# core-feather-shield-adc-imu-advanced_v1_.net
KiCad netlist of a schematic drawn in EAGLE
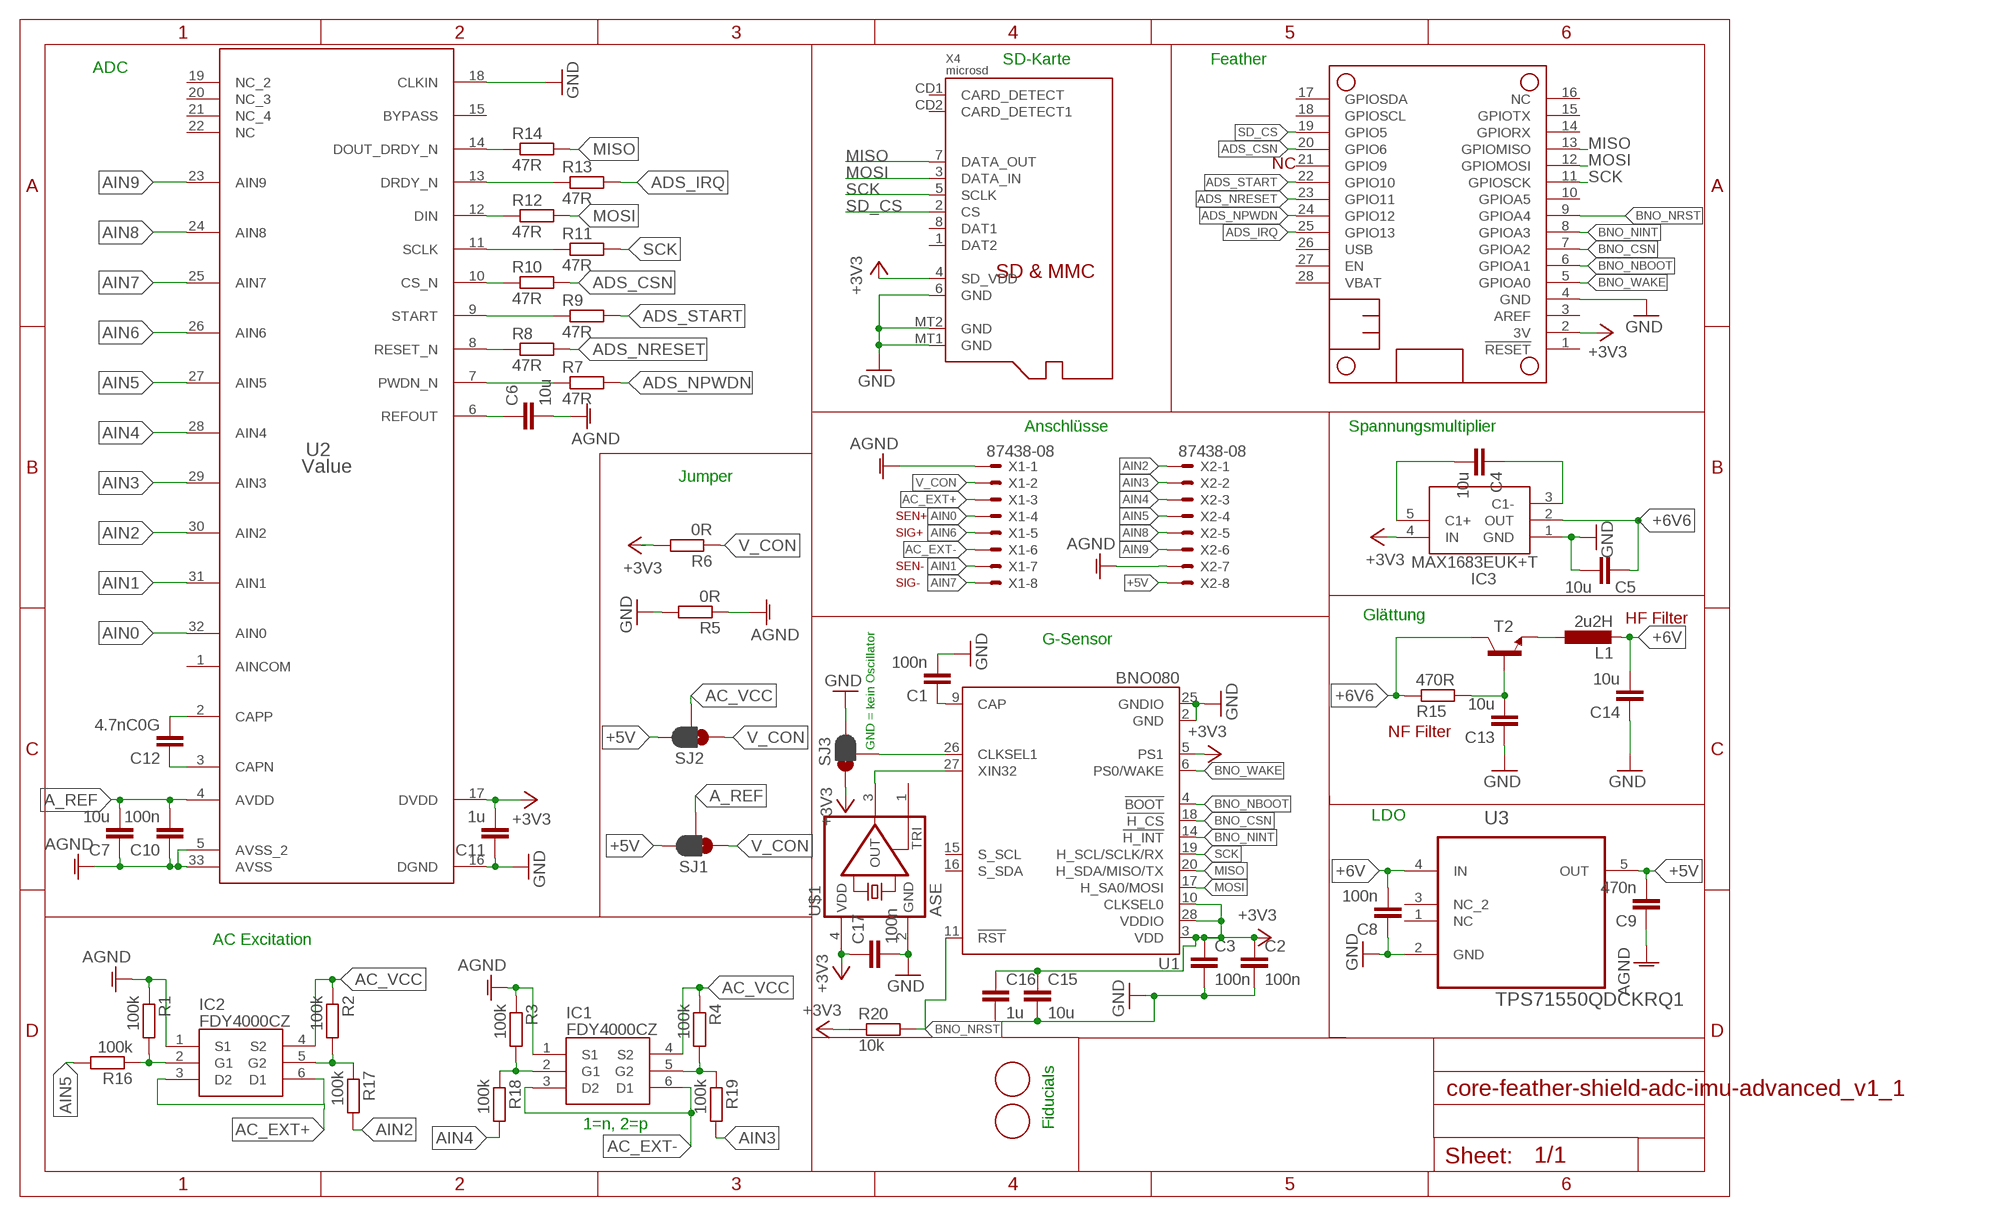
[diagram p0: schematic, sheet 1]

(export (version "E")
  (design (tool "Eeschema 10.0.6"))
  (components
    (comp (ref "C1")
      (value "100n")
      (footprint "eagle-import:C0805")
      (libsource (lib "eagle-import") (part "C-EUC0805"))
    )
    (comp (ref "C2")
      (value "100n")
      (footprint "eagle-import:C0805")
      (libsource (lib "eagle-import") (part "C-EUC0805"))
    )
    (comp (ref "C3")
      (value "100n")
      (footprint "eagle-import:C0805")
      (libsource (lib "eagle-import") (part "C-EUC0805"))
    )
    (comp (ref "C4")
      (value "10u")
      (footprint "eagle-import:C0805")
      (libsource (lib "eagle-import") (part "C-EUC0805"))
    )
    (comp (ref "C5")
      (value "10u")
      (footprint "eagle-import:C0805")
      (libsource (lib "eagle-import") (part "C-EUC0805"))
    )
    (comp (ref "C6")
      (value "10u")
      (footprint "eagle-import:C0805")
      (libsource (lib "eagle-import") (part "C-EUC0805"))
    )
    (comp (ref "C7")
      (value "10u")
      (footprint "eagle-import:C0805")
      (libsource (lib "eagle-import") (part "C-EUC0805"))
    )
    (comp (ref "C8")
      (value "100n")
      (footprint "eagle-import:C0805")
      (libsource (lib "eagle-import") (part "C-EUC0805"))
    )
    (comp (ref "C9")
      (value "470n")
      (footprint "eagle-import:C0805")
      (libsource (lib "eagle-import") (part "C-EUC0805"))
    )
    (comp (ref "C10")
      (value "100n")
      (footprint "eagle-import:C0805")
      (libsource (lib "eagle-import") (part "C-EUC0805"))
    )
    (comp (ref "C11")
      (value "1u")
      (footprint "eagle-import:C0805")
      (libsource (lib "eagle-import") (part "C-EUC0805"))
    )
    (comp (ref "C12")
      (value "4.7nC0G")
      (footprint "eagle-import:C0805")
      (libsource (lib "eagle-import") (part "C-EUC0805"))
    )
    (comp (ref "C13")
      (value "10u")
      (footprint "eagle-import:C0805")
      (libsource (lib "eagle-import") (part "C-EUC0805"))
    )
    (comp (ref "C14")
      (value "10u")
      (footprint "eagle-import:C0805")
      (libsource (lib "eagle-import") (part "C-EUC0805"))
    )
    (comp (ref "C15")
      (value "10u")
      (footprint "eagle-import:C0805")
      (libsource (lib "eagle-import") (part "C-EUC0805"))
    )
    (comp (ref "C16")
      (value "1u")
      (footprint "eagle-import:C0805")
      (libsource (lib "eagle-import") (part "C-EUC0805"))
    )
    (comp (ref "C17")
      (value "100n")
      (footprint "eagle-import:C0805")
      (libsource (lib "eagle-import") (part "C-EUC0805"))
    )
    (comp (ref "IC1")
      (value "FDY4000CZ")
      (footprint "eagle-import:SOTFL50P160X60-6N")
      (fields (field (name "MOUSER_PART_NUMBER") "512-FDY4000CZ") (field (name "RS_PART_NUMBER") "6710857"))
      (libsource (lib "eagle-import") (part "FDY4000CZ"))
    )
    (comp (ref "IC2")
      (value "FDY4000CZ")
      (footprint "eagle-import:SOTFL50P160X60-6N")
      (fields (field (name "MOUSER_PART_NUMBER") "512-FDY4000CZ") (field (name "RS_PART_NUMBER") "6710857"))
      (libsource (lib "eagle-import") (part "FDY4000CZ"))
    )
    (comp (ref "IC3")
      (value "MAX1683EUK+T")
      (footprint "eagle-import:SOT95P280X145-5N")
      (fields (field (name "MOUSER_PART_NUMBER") "700-MAX1683EUKT"))
      (libsource (lib "eagle-import") (part "MAX1683EUK+T"))
    )
    (comp (ref "L1")
      (value "2u2H")
      (footprint "eagle-import:L0805")
      (libsource (lib "eagle-import") (part "L-EUL0805"))
    )
    (comp (ref "MS1")
      (value "FEATHERWING")
      (footprint "eagle-import:FEATHERWING")
      (libsource (lib "eagle-import") (part "FEATHERWING"))
    )
    (comp (ref "R1")
      (value "100k")
      (footprint "eagle-import:R0805")
      (libsource (lib "eagle-import") (part "R-EU_R0805"))
    )
    (comp (ref "R2")
      (value "100k")
      (footprint "eagle-import:R0805")
      (libsource (lib "eagle-import") (part "R-EU_R0805"))
    )
    (comp (ref "R3")
      (value "100k")
      (footprint "eagle-import:R0805")
      (libsource (lib "eagle-import") (part "R-EU_R0805"))
    )
    (comp (ref "R4")
      (value "100k")
      (footprint "eagle-import:R0805")
      (libsource (lib "eagle-import") (part "R-EU_R0805"))
    )
    (comp (ref "R5")
      (value "0R")
      (footprint "eagle-import:R0805")
      (libsource (lib "eagle-import") (part "R-EU_R0805"))
    )
    (comp (ref "R6")
      (value "0R")
      (footprint "eagle-import:R0805")
      (libsource (lib "eagle-import") (part "R-EU_R0805"))
    )
    (comp (ref "R7")
      (value "47R")
      (footprint "eagle-import:R0805")
      (libsource (lib "eagle-import") (part "R-EU_R0805"))
    )
    (comp (ref "R8")
      (value "47R")
      (footprint "eagle-import:R0805")
      (libsource (lib "eagle-import") (part "R-EU_R0805"))
    )
    (comp (ref "R9")
      (value "47R")
      (footprint "eagle-import:R0805")
      (libsource (lib "eagle-import") (part "R-EU_R0805"))
    )
    (comp (ref "R10")
      (value "47R")
      (footprint "eagle-import:R0805")
      (libsource (lib "eagle-import") (part "R-EU_R0805"))
    )
    (comp (ref "R11")
      (value "47R")
      (footprint "eagle-import:R0805")
      (libsource (lib "eagle-import") (part "R-EU_R0805"))
    )
    (comp (ref "R12")
      (value "47R")
      (footprint "eagle-import:R0805")
      (libsource (lib "eagle-import") (part "R-EU_R0805"))
    )
    (comp (ref "R13")
      (value "47R")
      (footprint "eagle-import:R0805")
      (libsource (lib "eagle-import") (part "R-EU_R0805"))
    )
    (comp (ref "R14")
      (value "47R")
      (footprint "eagle-import:R0805")
      (libsource (lib "eagle-import") (part "R-EU_R0805"))
    )
    (comp (ref "R15")
      (value "470R")
      (footprint "eagle-import:R0805")
      (libsource (lib "eagle-import") (part "R-EU_R0805"))
    )
    (comp (ref "R16")
      (value "100k")
      (footprint "eagle-import:R0805")
      (libsource (lib "eagle-import") (part "R-EU_R0805"))
    )
    (comp (ref "R17")
      (value "100k")
      (footprint "eagle-import:R0805")
      (libsource (lib "eagle-import") (part "R-EU_R0805"))
    )
    (comp (ref "R18")
      (value "100k")
      (footprint "eagle-import:R0805")
      (libsource (lib "eagle-import") (part "R-EU_R0805"))
    )
    (comp (ref "R19")
      (value "100k")
      (footprint "eagle-import:R0805")
      (libsource (lib "eagle-import") (part "R-EU_R0805"))
    )
    (comp (ref "R20")
      (value "10k")
      (footprint "eagle-import:R0805")
      (libsource (lib "eagle-import") (part "R-EU_R0805"))
    )
    (comp (ref "SJ1")
      (value "JUMPER_PAD-3-1&2_NC_BY_PASTE")
      (footprint "eagle-import:PAD-HUMPER-3-1&2_NC_BY_PASTE_YES_SILK_FULL_BOX")
      (libsource (lib "eagle-import") (part "JUMPER_PAD-3-1&2_NC_BY_PASTE"))
    )
    (comp (ref "SJ2")
      (value "JUMPER_PAD-3-1&2_NC_BY_PASTE")
      (footprint "eagle-import:PAD-HUMPER-3-1&2_NC_BY_PASTE_YES_SILK_FULL_BOX")
      (libsource (lib "eagle-import") (part "JUMPER_PAD-3-1&2_NC_BY_PASTE"))
    )
    (comp (ref "SJ3")
      (value "JUMPER_PAD-3-1&2_NC_BY_PASTE")
      (footprint "eagle-import:PAD-HUMPER-3-1&2_NC_BY_PASTE_YES_SILK_FULL_BOX")
      (libsource (lib "eagle-import") (part "JUMPER_PAD-3-1&2_NC_BY_PASTE"))
    )
    (comp (ref "T2")
      (value "BC808-NPN-SOT23-BEC")
      (footprint "eagle-import:SOT23-BEC")
      (libsource (lib "eagle-import") (part "-NPN-SOT23-BECBC808"))
    )
    (comp (ref "U$1")
      (value "ASE")
      (footprint "eagle-import:ASE")
      (libsource (lib "eagle-import") (part "ASE"))
    )
    (comp (ref "U$8")
      (value "FIDUCIAL")
      (footprint "eagle-import:FIDUCIAL_1MM")
      (libsource (lib "eagle-import") (part "FIDUCIAL"))
    )
    (comp (ref "U$9")
      (value "FIDUCIAL")
      (footprint "eagle-import:FIDUCIAL_1MM")
      (libsource (lib "eagle-import") (part "FIDUCIAL"))
    )
    (comp (ref "U1")
      (value "BNO080")
      (footprint "eagle-import:LGA-28")
      (fields (field (name "MF") "Hillcrest Laboratories,"))
      (libsource (lib "eagle-import") (part "BNO080"))
    )
    (comp (ref "U2")
      (value "Value")
      (footprint "eagle-import:RHB0032E")
      (fields (field (name "MANUFACTURER") "Texas Instruments") (field (name "PARTNUMBER") "ADS1261IRHBR"))
      (libsource (lib "eagle-import") (part "ADS1261IRHBR"))
    )
    (comp (ref "U3")
      (value "TPS71550QDCKRQ1")
      (footprint "eagle-import:SOT65P210X110-5N")
      (fields (field (name "MF") "Texas Instruments"))
      (libsource (lib "eagle-import") (part "TPS71550QDCKRQ1"))
    )
    (comp (ref "X1")
      (value "87438-08")
      (footprint "eagle-import:87438-08")
      (fields (field (name "MF") "MOLEX") (field (name "SPICEPREFIX") "X"))
      (libsource (lib "eagle-import") (part "87438-08"))
    )
    (comp (ref "X2")
      (value "87438-08")
      (footprint "eagle-import:87438-08")
      (fields (field (name "MF") "MOLEX") (field (name "SPICEPREFIX") "X"))
      (libsource (lib "eagle-import") (part "87438-08"))
    )
    (comp (ref "X4")
      (value "microsd")
      (footprint "eagle-import:MICROSD")
      (libsource (lib "eagle-import") (part "MICROSD"))
    )
  )
  (nets
    (net (code "1") (name "+3V3") (class "Default")
      (node (ref "C11") (pin "2") (pinfunction "2_2") (pintype "passive"))
      (node (ref "C15") (pin "1") (pinfunction "1_1") (pintype "passive"))
      (node (ref "C16") (pin "1") (pinfunction "1_1") (pintype "passive"))
      (node (ref "C17") (pin "1") (pinfunction "1_1") (pintype "passive"))
      (node (ref "C2") (pin "1") (pinfunction "1_1") (pintype "passive"))
      (node (ref "C3") (pin "1") (pinfunction "1_1") (pintype "passive"))
      (node (ref "IC3") (pin "4") (pinfunction "IN_4") (pintype "input"))
      (node (ref "MS1") (pin "2") (pinfunction "3V_2") (pintype "power_in"))
      (node (ref "R20") (pin "1") (pinfunction "1_1") (pintype "passive"))
      (node (ref "R6") (pin "2") (pinfunction "2_2") (pintype "passive"))
      (node (ref "SJ3") (pin "3") (pinfunction "3_3") (pintype "passive"))
      (node (ref "U$1") (pin "4") (pinfunction "VDD_4") (pintype "power_in"))
      (node (ref "U1") (pin "10") (pinfunction "CLKSEL0_10") (pintype "bidirectional"))
      (node (ref "U1") (pin "28") (pinfunction "VDDIO_28") (pintype "bidirectional"))
      (node (ref "U1") (pin "3") (pinfunction "VDD_3") (pintype "bidirectional"))
      (node (ref "U1") (pin "5") (pinfunction "PS1_5") (pintype "bidirectional"))
      (node (ref "U2") (pin "17") (pinfunction "DVDD_17") (pintype "power_in"))
      (node (ref "X4") (pin "4") (pinfunction "SD_VDD_4") (pintype "power_in"))
    )
    (net (code "2") (name "+5V") (class "Default")
      (node (ref "C9") (pin "2") (pinfunction "2_2") (pintype "passive"))
      (node (ref "SJ1") (pin "1") (pinfunction "1_1") (pintype "passive"))
      (node (ref "SJ2") (pin "1") (pinfunction "1_1") (pintype "passive"))
      (node (ref "U3") (pin "5") (pinfunction "OUT_5") (pintype "output"))
      (node (ref "X2") (pin "8") (pinfunction "S_8") (pintype "passive"))
    )
    (net (code "3") (name "+6V") (class "Default")
      (node (ref "C14") (pin "2") (pinfunction "2_2") (pintype "passive"))
      (node (ref "C8") (pin "2") (pinfunction "2_2") (pintype "passive"))
      (node (ref "L1") (pin "2") (pinfunction "2_2") (pintype "passive"))
      (node (ref "U3") (pin "4") (pinfunction "IN_4") (pintype "power_in"))
    )
    (net (code "4") (name "+6V6") (class "Default")
      (node (ref "C5") (pin "1") (pinfunction "1_1") (pintype "passive"))
      (node (ref "IC3") (pin "2") (pinfunction "OUT_2") (pintype "output"))
      (node (ref "R15") (pin "2") (pinfunction "2_2") (pintype "passive"))
      (node (ref "T2") (pin "C") (pinfunction "C_C") (pintype "passive"))
    )
    (net (code "5") (name "/USB") (class "Default")
      (node (ref "MS1") (pin "26") (pinfunction "USB_26") (pintype "power_in"))
    )
    (net (code "6") (name "/VBAT") (class "Default")
      (node (ref "MS1") (pin "28") (pinfunction "VBAT_28") (pintype "power_in"))
    )
    (net (code "7") (name "AC_EXT+") (class "Default")
      (node (ref "IC2") (pin "3") (pinfunction "D2_3") (pintype "bidirectional"))
      (node (ref "IC2") (pin "6") (pinfunction "D1_6") (pintype "bidirectional"))
      (node (ref "X1") (pin "3") (pinfunction "S_3") (pintype "passive"))
    )
    (net (code "8") (name "AC_EXT-") (class "Default")
      (node (ref "IC1") (pin "3") (pinfunction "D2_3") (pintype "bidirectional"))
      (node (ref "IC1") (pin "6") (pinfunction "D1_6") (pintype "bidirectional"))
      (node (ref "X1") (pin "6") (pinfunction "S_6") (pintype "passive"))
    )
    (net (code "9") (name "AC_VCC") (class "Default")
      (node (ref "IC1") (pin "4") (pinfunction "S2_4") (pintype "bidirectional"))
      (node (ref "IC2") (pin "4") (pinfunction "S2_4") (pintype "bidirectional"))
      (node (ref "R2") (pin "1") (pinfunction "1_1") (pintype "passive"))
      (node (ref "R4") (pin "1") (pinfunction "1_1") (pintype "passive"))
      (node (ref "SJ2") (pin "2") (pinfunction "2_2") (pintype "passive"))
    )
    (net (code "10") (name "ADS_CSN") (class "Default")
      (node (ref "MS1") (pin "20") (pinfunction "GPIO6_20") (pintype "bidirectional"))
      (node (ref "R10") (pin "2") (pinfunction "2_2") (pintype "passive"))
    )
    (net (code "11") (name "ADS_IRQ") (class "Default")
      (node (ref "MS1") (pin "25") (pinfunction "GPIO13_25") (pintype "bidirectional"))
      (node (ref "R13") (pin "2") (pinfunction "2_2") (pintype "passive"))
    )
    (net (code "12") (name "ADS_NPWDN") (class "Default")
      (node (ref "MS1") (pin "24") (pinfunction "GPIO12_24") (pintype "bidirectional"))
      (node (ref "R7") (pin "2") (pinfunction "2_2") (pintype "passive"))
    )
    (net (code "13") (name "ADS_NRESET") (class "Default")
      (node (ref "MS1") (pin "23") (pinfunction "GPIO11_23") (pintype "bidirectional"))
      (node (ref "R8") (pin "2") (pinfunction "2_2") (pintype "passive"))
    )
    (net (code "14") (name "ADS_START") (class "Default")
      (node (ref "MS1") (pin "22") (pinfunction "GPIO10_22") (pintype "bidirectional"))
      (node (ref "R9") (pin "2") (pinfunction "2_2") (pintype "passive"))
    )
    (net (code "15") (name "AGND") (class "Default")
      (node (ref "C10") (pin "1") (pinfunction "1_1") (pintype "passive"))
      (node (ref "C6") (pin "2") (pinfunction "2_2") (pintype "passive"))
      (node (ref "C7") (pin "1") (pinfunction "1_1") (pintype "passive"))
      (node (ref "C9") (pin "1") (pinfunction "1_1") (pintype "passive"))
      (node (ref "IC1") (pin "1") (pinfunction "S1_1") (pintype "bidirectional"))
      (node (ref "IC2") (pin "1") (pinfunction "S1_1") (pintype "bidirectional"))
      (node (ref "R1") (pin "1") (pinfunction "1_1") (pintype "passive"))
      (node (ref "R3") (pin "1") (pinfunction "1_1") (pintype "passive"))
      (node (ref "R5") (pin "1") (pinfunction "1_1") (pintype "passive"))
      (node (ref "U2") (pin "33") (pinfunction "AVSS_33") (pintype "power_in"))
      (node (ref "U2") (pin "5") (pinfunction "AVSS_2_5") (pintype "power_in"))
      (node (ref "X1") (pin "1") (pinfunction "S_1") (pintype "passive"))
      (node (ref "X2") (pin "7") (pinfunction "S_7") (pintype "passive"))
    )
    (net (code "16") (name "AIN0") (class "Default")
      (node (ref "U2") (pin "32") (pinfunction "AIN0_32") (pintype "input"))
      (node (ref "X1") (pin "4") (pinfunction "S_4") (pintype "passive"))
    )
    (net (code "17") (name "AIN1") (class "Default")
      (node (ref "U2") (pin "31") (pinfunction "AIN1_31") (pintype "input"))
      (node (ref "X1") (pin "7") (pinfunction "S_7") (pintype "passive"))
    )
    (net (code "18") (name "AIN2") (class "Default")
      (node (ref "R17") (pin "2") (pinfunction "2_2") (pintype "passive"))
      (node (ref "U2") (pin "30") (pinfunction "AIN2_30") (pintype "input"))
      (node (ref "X2") (pin "1") (pinfunction "S_1") (pintype "passive"))
    )
    (net (code "19") (name "AIN3") (class "Default")
      (node (ref "R19") (pin "2") (pinfunction "2_2") (pintype "passive"))
      (node (ref "U2") (pin "29") (pinfunction "AIN3_29") (pintype "input"))
      (node (ref "X2") (pin "2") (pinfunction "S_2") (pintype "passive"))
    )
    (net (code "20") (name "AIN4") (class "Default")
      (node (ref "R18") (pin "2") (pinfunction "2_2") (pintype "passive"))
      (node (ref "U2") (pin "28") (pinfunction "AIN4_28") (pintype "input"))
      (node (ref "X2") (pin "3") (pinfunction "S_3") (pintype "passive"))
    )
    (net (code "21") (name "AIN5") (class "Default")
      (node (ref "R16") (pin "2") (pinfunction "2_2") (pintype "passive"))
      (node (ref "U2") (pin "27") (pinfunction "AIN5_27") (pintype "input"))
      (node (ref "X2") (pin "4") (pinfunction "S_4") (pintype "passive"))
    )
    (net (code "22") (name "AIN6") (class "Default")
      (node (ref "U2") (pin "26") (pinfunction "AIN6_26") (pintype "input"))
      (node (ref "X1") (pin "5") (pinfunction "S_5") (pintype "passive"))
    )
    (net (code "23") (name "AIN7") (class "Default")
      (node (ref "U2") (pin "25") (pinfunction "AIN7_25") (pintype "input"))
      (node (ref "X1") (pin "8") (pinfunction "S_8") (pintype "passive"))
    )
    (net (code "24") (name "AIN8") (class "Default")
      (node (ref "U2") (pin "24") (pinfunction "AIN8_24") (pintype "input"))
      (node (ref "X2") (pin "5") (pinfunction "S_5") (pintype "passive"))
    )
    (net (code "25") (name "AIN9") (class "Default")
      (node (ref "U2") (pin "23") (pinfunction "AIN9_23") (pintype "input"))
      (node (ref "X2") (pin "6") (pinfunction "S_6") (pintype "passive"))
    )
    (net (code "26") (name "A_REF") (class "Default")
      (node (ref "C10") (pin "2") (pinfunction "2_2") (pintype "passive"))
      (node (ref "C7") (pin "2") (pinfunction "2_2") (pintype "passive"))
      (node (ref "SJ1") (pin "2") (pinfunction "2_2") (pintype "passive"))
      (node (ref "U2") (pin "4") (pinfunction "AVDD_4") (pintype "power_in"))
    )
    (net (code "27") (name "BNO_CSN") (class "Default")
      (node (ref "MS1") (pin "7") (pinfunction "GPIOA2_7") (pintype "bidirectional"))
      (node (ref "U1") (pin "18") (pinfunction "~{H_CS}_18") (pintype "bidirectional"))
    )
    (net (code "28") (name "BNO_NBOOT") (class "Default")
      (node (ref "MS1") (pin "6") (pinfunction "GPIOA1_6") (pintype "bidirectional"))
      (node (ref "U1") (pin "4") (pinfunction "~{BOOT}_4") (pintype "bidirectional"))
    )
    (net (code "29") (name "BNO_NINT") (class "Default")
      (node (ref "MS1") (pin "8") (pinfunction "GPIOA3_8") (pintype "bidirectional"))
      (node (ref "U1") (pin "14") (pinfunction "~{H_INT}_14") (pintype "bidirectional"))
    )
    (net (code "30") (name "BNO_NRST") (class "Default")
      (node (ref "MS1") (pin "9") (pinfunction "GPIOA4_9") (pintype "bidirectional"))
      (node (ref "R20") (pin "2") (pinfunction "2_2") (pintype "passive"))
      (node (ref "U1") (pin "11") (pinfunction "~{RST}_11") (pintype "bidirectional"))
    )
    (net (code "31") (name "BNO_WAKE") (class "Default")
      (node (ref "MS1") (pin "5") (pinfunction "GPIOA0_5") (pintype "bidirectional"))
      (node (ref "U1") (pin "6") (pinfunction "PS0/WAKE_6") (pintype "bidirectional"))
    )
    (net (code "32") (name "GND") (class "Default")
      (node (ref "C1") (pin "2") (pinfunction "2_2") (pintype "passive"))
      (node (ref "C11") (pin "1") (pinfunction "1_1") (pintype "passive"))
      (node (ref "C13") (pin "1") (pinfunction "1_1") (pintype "passive"))
      (node (ref "C14") (pin "1") (pinfunction "1_1") (pintype "passive"))
      (node (ref "C15") (pin "2") (pinfunction "2_2") (pintype "passive"))
      (node (ref "C16") (pin "2") (pinfunction "2_2") (pintype "passive"))
      (node (ref "C17") (pin "2") (pinfunction "2_2") (pintype "passive"))
      (node (ref "C2") (pin "2") (pinfunction "2_2") (pintype "passive"))
      (node (ref "C3") (pin "2") (pinfunction "2_2") (pintype "passive"))
      (node (ref "C5") (pin "2") (pinfunction "2_2") (pintype "passive"))
      (node (ref "C8") (pin "1") (pinfunction "1_1") (pintype "passive"))
      (node (ref "IC3") (pin "1") (pinfunction "GND_1") (pintype "power_in"))
      (node (ref "MS1") (pin "4") (pinfunction "GND_4") (pintype "power_in"))
      (node (ref "R5") (pin "2") (pinfunction "2_2") (pintype "passive"))
      (node (ref "SJ3") (pin "1") (pinfunction "1_1") (pintype "passive"))
      (node (ref "U$1") (pin "2") (pinfunction "GND_2") (pintype "power_in"))
      (node (ref "U1") (pin "2") (pinfunction "GND_2") (pintype "bidirectional"))
      (node (ref "U1") (pin "25") (pinfunction "GNDIO_25") (pintype "bidirectional"))
      (node (ref "U2") (pin "16") (pinfunction "DGND_16") (pintype "power_in"))
      (node (ref "U2") (pin "18") (pinfunction "CLKIN_18") (pintype "input"))
      (node (ref "U3") (pin "2") (pinfunction "GND_2") (pintype "passive"))
      (node (ref "X4") (pin "6") (pinfunction "GND_6") (pintype "power_in"))
      (node (ref "X4") (pin "MT1") (pinfunction "GND_MT1") (pintype "power_in"))
      (node (ref "X4") (pin "MT2") (pinfunction "GND_MT2") (pintype "power_in"))
    )
    (net (code "33") (name "MISO") (class "Default")
      (node (ref "MS1") (pin "13") (pinfunction "GPIOMISO_13") (pintype "bidirectional"))
      (node (ref "R14") (pin "2") (pinfunction "2_2") (pintype "passive"))
      (node (ref "U1") (pin "20") (pinfunction "H_SDA/MISO/TX_20") (pintype "bidirectional"))
      (node (ref "X4") (pin "7") (pinfunction "DATA_OUT_7") (pintype "output"))
    )
    (net (code "34") (name "MOSI") (class "Default")
      (node (ref "MS1") (pin "12") (pinfunction "GPIOMOSI_12") (pintype "bidirectional"))
      (node (ref "R12") (pin "2") (pinfunction "2_2") (pintype "passive"))
      (node (ref "U1") (pin "17") (pinfunction "H_SA0/MOSI_17") (pintype "bidirectional"))
      (node (ref "X4") (pin "3") (pinfunction "DATA_IN_3") (pintype "input"))
    )
    (net (code "35") (name "Net-(C13-Pad2)") (class "Default")
      (node (ref "C13") (pin "2") (pinfunction "2_2") (pintype "passive"))
      (node (ref "R15") (pin "1") (pinfunction "1_1") (pintype "passive"))
      (node (ref "T2") (pin "B") (pinfunction "B_B") (pintype "passive"))
    )
    (net (code "36") (name "Net-(IC1-G1)") (class "Default")
      (node (ref "IC1") (pin "2") (pinfunction "G1_2") (pintype "bidirectional"))
      (node (ref "R18") (pin "1") (pinfunction "1_1") (pintype "passive"))
      (node (ref "R3") (pin "2") (pinfunction "2_2") (pintype "passive"))
    )
    (net (code "37") (name "Net-(IC1-G2)") (class "Default")
      (node (ref "IC1") (pin "5") (pinfunction "G2_5") (pintype "bidirectional"))
      (node (ref "R19") (pin "1") (pinfunction "1_1") (pintype "passive"))
      (node (ref "R4") (pin "2") (pinfunction "2_2") (pintype "passive"))
    )
    (net (code "38") (name "Net-(IC2-G1)") (class "Default")
      (node (ref "IC2") (pin "2") (pinfunction "G1_2") (pintype "bidirectional"))
      (node (ref "R1") (pin "2") (pinfunction "2_2") (pintype "passive"))
      (node (ref "R16") (pin "1") (pinfunction "1_1") (pintype "passive"))
    )
    (net (code "39") (name "Net-(IC2-G2)") (class "Default")
      (node (ref "IC2") (pin "5") (pinfunction "G2_5") (pintype "bidirectional"))
      (node (ref "R17") (pin "1") (pinfunction "1_1") (pintype "passive"))
      (node (ref "R2") (pin "2") (pinfunction "2_2") (pintype "passive"))
    )
    (net (code "40") (name "Net-(IC3-C1+)") (class "Default")
      (node (ref "C4") (pin "2") (pinfunction "2_2") (pintype "passive"))
      (node (ref "IC3") (pin "5") (pinfunction "C1+_5") (pintype "bidirectional"))
    )
    (net (code "41") (name "Net-(IC3-C1-)") (class "Default")
      (node (ref "C4") (pin "1") (pinfunction "1_1") (pintype "passive"))
      (node (ref "IC3") (pin "3") (pinfunction "C1-_3") (pintype "bidirectional"))
    )
    (net (code "42") (name "Net-(L1-Pad1)") (class "Default")
      (node (ref "L1") (pin "1") (pinfunction "1_1") (pintype "passive"))
      (node (ref "T2") (pin "E") (pinfunction "E_E") (pintype "passive"))
    )
    (net (code "43") (name "Net-(U$1-OUT)") (class "Default")
      (node (ref "U$1") (pin "3") (pinfunction "OUT_3") (pintype "output"))
      (node (ref "U1") (pin "27") (pinfunction "XIN32_27") (pintype "bidirectional"))
    )
    (net (code "44") (name "Net-(U1-CAP)") (class "Default")
      (node (ref "C1") (pin "1") (pinfunction "1_1") (pintype "passive"))
      (node (ref "U1") (pin "9") (pinfunction "CAP_9") (pintype "bidirectional"))
    )
    (net (code "45") (name "Net-(U1-CLKSEL1)") (class "Default")
      (node (ref "SJ3") (pin "2") (pinfunction "2_2") (pintype "passive"))
      (node (ref "U1") (pin "26") (pinfunction "CLKSEL1_26") (pintype "bidirectional"))
    )
    (net (code "46") (name "Net-(U2-CAPN)") (class "Default")
      (node (ref "C12") (pin "1") (pinfunction "1_1") (pintype "passive"))
      (node (ref "U2") (pin "3") (pinfunction "CAPN_3") (pintype "passive"))
    )
    (net (code "47") (name "Net-(U2-CAPP)") (class "Default")
      (node (ref "C12") (pin "2") (pinfunction "2_2") (pintype "passive"))
      (node (ref "U2") (pin "2") (pinfunction "CAPP_2") (pintype "passive"))
    )
    (net (code "48") (name "Net-(U2-CS_N)") (class "Default")
      (node (ref "R10") (pin "1") (pinfunction "1_1") (pintype "passive"))
      (node (ref "U2") (pin "10") (pinfunction "CS_N_10") (pintype "input"))
    )
    (net (code "49") (name "Net-(U2-DIN)") (class "Default")
      (node (ref "R12") (pin "1") (pinfunction "1_1") (pintype "passive"))
      (node (ref "U2") (pin "12") (pinfunction "DIN_12") (pintype "input"))
    )
    (net (code "50") (name "Net-(U2-DOUT_DRDY_N)") (class "Default")
      (node (ref "R14") (pin "1") (pinfunction "1_1") (pintype "passive"))
      (node (ref "U2") (pin "14") (pinfunction "DOUT_DRDY_N_14") (pintype "output"))
    )
    (net (code "51") (name "Net-(U2-DRDY_N)") (class "Default")
      (node (ref "R13") (pin "1") (pinfunction "1_1") (pintype "passive"))
      (node (ref "U2") (pin "13") (pinfunction "DRDY_N_13") (pintype "output"))
    )
    (net (code "52") (name "Net-(U2-PWDN_N)") (class "Default")
      (node (ref "R7") (pin "1") (pinfunction "1_1") (pintype "passive"))
      (node (ref "U2") (pin "7") (pinfunction "PWDN_N_7") (pintype "input"))
    )
    (net (code "53") (name "Net-(U2-REFOUT)") (class "Default")
      (node (ref "C6") (pin "1") (pinfunction "1_1") (pintype "passive"))
      (node (ref "U2") (pin "6") (pinfunction "REFOUT_6") (pintype "output"))
    )
    (net (code "54") (name "Net-(U2-RESET_N)") (class "Default")
      (node (ref "R8") (pin "1") (pinfunction "1_1") (pintype "passive"))
      (node (ref "U2") (pin "8") (pinfunction "RESET_N_8") (pintype "input"))
    )
    (net (code "55") (name "Net-(U2-SCLK)") (class "Default")
      (node (ref "R11") (pin "1") (pinfunction "1_1") (pintype "passive"))
      (node (ref "U2") (pin "11") (pinfunction "SCLK_11") (pintype "input"))
    )
    (net (code "56") (name "Net-(U2-START)") (class "Default")
      (node (ref "R9") (pin "1") (pinfunction "1_1") (pintype "passive"))
      (node (ref "U2") (pin "9") (pinfunction "START_9") (pintype "input"))
    )
    (net (code "57") (name "SCK") (class "Default")
      (node (ref "MS1") (pin "11") (pinfunction "GPIOSCK_11") (pintype "bidirectional"))
      (node (ref "R11") (pin "2") (pinfunction "2_2") (pintype "passive"))
      (node (ref "U1") (pin "19") (pinfunction "H_SCL/SCLK/RX_19") (pintype "bidirectional"))
      (node (ref "X4") (pin "5") (pinfunction "SCLK_5") (pintype "input"))
    )
    (net (code "58") (name "SD_CS") (class "Default")
      (node (ref "MS1") (pin "19") (pinfunction "GPIO5_19") (pintype "bidirectional"))
      (node (ref "X4") (pin "2") (pinfunction "CS_2") (pintype "input"))
    )
    (net (code "59") (name "V_CON") (class "Default")
      (node (ref "R6") (pin "1") (pinfunction "1_1") (pintype "passive"))
      (node (ref "SJ1") (pin "3") (pinfunction "3_3") (pintype "passive"))
      (node (ref "SJ2") (pin "3") (pinfunction "3_3") (pintype "passive"))
      (node (ref "X1") (pin "2") (pinfunction "S_2") (pintype "passive"))
    )
    (net (code "60") (name "unconnected-(MS1-AREF-Pad3)") (class "Default")
      (node (ref "MS1") (pin "3") (pinfunction "AREF_3") (pintype "passive"))
    )
    (net (code "61") (name "unconnected-(MS1-EN-Pad27)") (class "Default")
      (node (ref "MS1") (pin "27") (pinfunction "EN_27") (pintype "passive"))
    )
    (net (code "62") (name "unconnected-(MS1-GPIO9-Pad21)") (class "Default")
      (node (ref "MS1") (pin "21") (pinfunction "GPIO9_21") (pintype "bidirectional"))
    )
    (net (code "63") (name "unconnected-(MS1-GPIOA5-Pad10)") (class "Default")
      (node (ref "MS1") (pin "10") (pinfunction "GPIOA5_10") (pintype "bidirectional"))
    )
    (net (code "64") (name "unconnected-(MS1-GPIORX-Pad14)") (class "Default")
      (node (ref "MS1") (pin "14") (pinfunction "GPIORX_14") (pintype "bidirectional"))
    )
    (net (code "65") (name "unconnected-(MS1-GPIOSCL-Pad18)") (class "Default")
      (node (ref "MS1") (pin "18") (pinfunction "GPIOSCL_18") (pintype "bidirectional"))
    )
    (net (code "66") (name "unconnected-(MS1-GPIOSDA-Pad17)") (class "Default")
      (node (ref "MS1") (pin "17") (pinfunction "GPIOSDA_17") (pintype "bidirectional"))
    )
    (net (code "67") (name "unconnected-(MS1-GPIOTX-Pad15)") (class "Default")
      (node (ref "MS1") (pin "15") (pinfunction "GPIOTX_15") (pintype "bidirectional"))
    )
    (net (code "68") (name "unconnected-(MS1-NC-Pad16)") (class "Default")
      (node (ref "MS1") (pin "16") (pinfunction "NC_16") (pintype "passive"))
    )
    (net (code "69") (name "unconnected-(MS1-~{RESET}-Pad1)") (class "Default")
      (node (ref "MS1") (pin "1") (pinfunction "~{RESET}_1") (pintype "input"))
    )
    (net (code "70") (name "unconnected-(U$1-TRI-Pad1)") (class "Default")
      (node (ref "U$1") (pin "1") (pinfunction "TRI_1") (pintype "input"))
    )
    (net (code "71") (name "unconnected-(U1-S_SCL-Pad15)") (class "Default")
      (node (ref "U1") (pin "15") (pinfunction "S_SCL_15") (pintype "bidirectional"))
    )
    (net (code "72") (name "unconnected-(U1-S_SDA-Pad16)") (class "Default")
      (node (ref "U1") (pin "16") (pinfunction "S_SDA_16") (pintype "bidirectional"))
    )
    (net (code "73") (name "unconnected-(U2-AINCOM-Pad1)") (class "Default")
      (node (ref "U2") (pin "1") (pinfunction "AINCOM_1") (pintype "input"))
    )
    (net (code "74") (name "unconnected-(U2-BYPASS-Pad15)") (class "Default")
      (node (ref "U2") (pin "15") (pinfunction "BYPASS_15") (pintype "passive"))
    )
    (net (code "75") (name "unconnected-(U2-NC-Pad22)") (class "Default")
      (node (ref "U2") (pin "22") (pinfunction "NC_22") (pintype "passive"))
    )
    (net (code "76") (name "unconnected-(U2-NC_2-Pad19)") (class "Default")
      (node (ref "U2") (pin "19") (pinfunction "NC_2_19") (pintype "passive"))
    )
    (net (code "77") (name "unconnected-(U2-NC_3-Pad20)") (class "Default")
      (node (ref "U2") (pin "20") (pinfunction "NC_3_20") (pintype "passive"))
    )
    (net (code "78") (name "unconnected-(U2-NC_4-Pad21)") (class "Default")
      (node (ref "U2") (pin "21") (pinfunction "NC_4_21") (pintype "passive"))
    )
    (net (code "79") (name "unconnected-(U3-NC-Pad1)") (class "Default")
      (node (ref "U3") (pin "1") (pinfunction "NC_1") (pintype "no_connect"))
    )
    (net (code "80") (name "unconnected-(U3-NC_2-Pad3)") (class "Default")
      (node (ref "U3") (pin "3") (pinfunction "NC_2_3") (pintype "no_connect"))
    )
    (net (code "81") (name "unconnected-(X4-CARD_DETECT-PadCD1)") (class "Default")
      (node (ref "X4") (pin "CD1") (pinfunction "CARD_DETECT_CD1") (pintype "passive"))
    )
    (net (code "82") (name "unconnected-(X4-CARD_DETECT1-PadCD2)") (class "Default")
      (node (ref "X4") (pin "CD2") (pinfunction "CARD_DETECT1_CD2") (pintype "passive"))
    )
    (net (code "83") (name "unconnected-(X4-DAT1-Pad8)") (class "Default")
      (node (ref "X4") (pin "8") (pinfunction "DAT1_8") (pintype "bidirectional"))
    )
    (net (code "84") (name "unconnected-(X4-DAT2-Pad1)") (class "Default")
      (node (ref "X4") (pin "1") (pinfunction "DAT2_1") (pintype "bidirectional"))
    )
  )
)
